# Pi_Interface.net
KiCad netlist of a schematic drawn in EAGLE
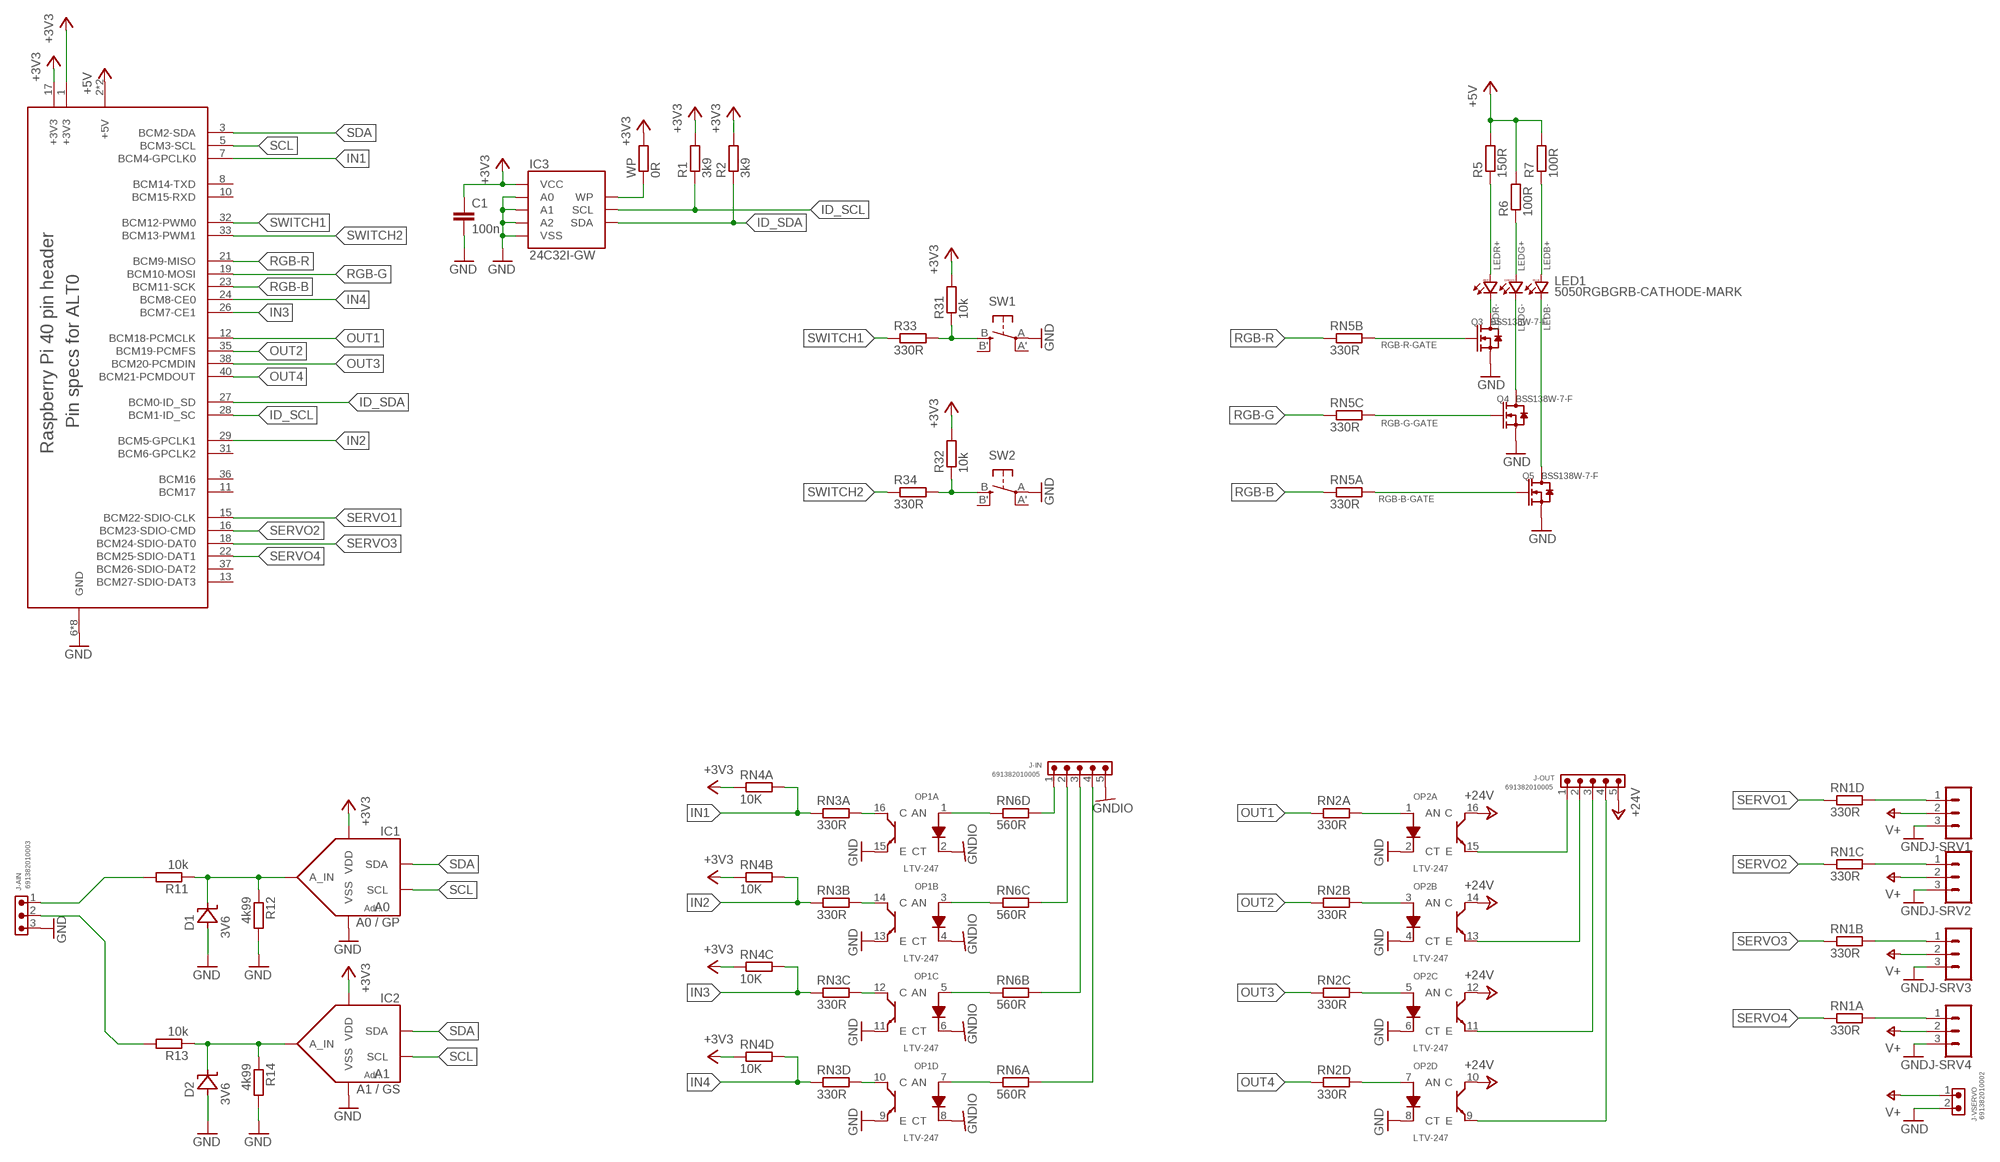
[diagram p0: schematic, sheet 1]

(export (version "E")
  (design (tool "Eeschema 10.0.6"))
  (components
    (comp (ref "C1")
      (value "100n")
      (footprint "eagle-import:C0603")
      (libsource (lib "eagle-import") (part "C-EUC0603"))
    )
    (comp (ref "D1")
      (value "3V6")
      (footprint "eagle-import:SOD3716X115N")
      (libsource (lib "eagle-import") (part "ZENERSOD-123"))
    )
    (comp (ref "D2")
      (value "3V6")
      (footprint "eagle-import:SOD3716X115N")
      (libsource (lib "eagle-import") (part "ZENERSOD-123"))
    )
    (comp (ref "IC1")
      (value "A0 / GP")
      (footprint "eagle-import:SOT95P280X145-5N")
      (fields (field (name "ADR") "A0"))
      (libsource (lib "eagle-import") (part "MCP3021T-E/OTA0"))
    )
    (comp (ref "IC2")
      (value "A1 / GS")
      (footprint "eagle-import:SOT95P280X145-5N")
      (fields (field (name "ADR") "A1"))
      (libsource (lib "eagle-import") (part "MCP3021T-E/OTA1"))
    )
    (comp (ref "IC3")
      (value "24C32I-GW")
      (footprint "eagle-import:SOIC127P600X175-8N")
      (libsource (lib "eagle-import") (part "24C32WI-G"))
    )
    (comp (ref "J-AIN")
      (value "691382010003")
      (footprint "eagle-import:691382010003")
      (libsource (lib "eagle-import") (part "691382010003"))
    )
    (comp (ref "J-IN")
      (value "691382010005")
      (footprint "eagle-import:691382010005")
      (libsource (lib "eagle-import") (part "691382010005"))
    )
    (comp (ref "J-OUT")
      (value "691382010005")
      (footprint "eagle-import:691382010005")
      (libsource (lib "eagle-import") (part "691382010005"))
    )
    (comp (ref "J-SRV1")
      (value "MA03-1")
      (footprint "eagle-import:MA03-1")
      (libsource (lib "eagle-import") (part "MA03-1"))
    )
    (comp (ref "J-SRV2")
      (value "MA03-1")
      (footprint "eagle-import:MA03-1")
      (libsource (lib "eagle-import") (part "MA03-1"))
    )
    (comp (ref "J-SRV3")
      (value "MA03-1")
      (footprint "eagle-import:MA03-1")
      (libsource (lib "eagle-import") (part "MA03-1"))
    )
    (comp (ref "J-SRV4")
      (value "MA03-1")
      (footprint "eagle-import:MA03-1")
      (libsource (lib "eagle-import") (part "MA03-1"))
    )
    (comp (ref "J-VSERVO")
      (value "691382010002")
      (footprint "eagle-import:691382010002")
      (libsource (lib "eagle-import") (part "691382010002"))
    )
    (comp (ref "J3")
      (value "RASPI-40HAT")
      (footprint "eagle-import:FE20-2")
      (libsource (lib "eagle-import") (part "RASPI-40HAT"))
    )
    (comp (ref "LED1")
      (value "5050RGBGRB-CATHODE-MARK")
      (footprint "eagle-import:CATH_MARK_5050_PLCC6")
      (libsource (lib "eagle-import") (part "5050RGBGRB-CATHODE-MARK"))
    )
    (comp (ref "OP1")
      (value "LTV-247")
      (footprint "eagle-import:SOIC127P675X220-16N")
      (fields (field (name "LCSC_PART") "C115451"))
      (libsource (lib "eagle-import") (part "LTV-247"))
    )
    (comp (ref "OP2")
      (value "LTV-247")
      (footprint "eagle-import:SOIC127P675X220-16N")
      (fields (field (name "LCSC_PART") "C115451"))
      (libsource (lib "eagle-import") (part "LTV-247"))
    )
    (comp (ref "Q3")
      (value "BSS138W-7-F")
      (footprint "eagle-import:SOT-23")
      (libsource (lib "eagle-import") (part "SMD-MOSFET-N-CH-50V-200MA-BSS138W-7-F(SOT-23)"))
    )
    (comp (ref "Q4")
      (value "BSS138W-7-F")
      (footprint "eagle-import:SOT-23")
      (libsource (lib "eagle-import") (part "SMD-MOSFET-N-CH-50V-200MA-BSS138W-7-F(SOT-23)"))
    )
    (comp (ref "Q5")
      (value "BSS138W-7-F")
      (footprint "eagle-import:SOT-23")
      (libsource (lib "eagle-import") (part "SMD-MOSFET-N-CH-50V-200MA-BSS138W-7-F(SOT-23)"))
    )
    (comp (ref "R1")
      (value "3k9")
      (footprint "eagle-import:R0603")
      (libsource (lib "eagle-import") (part "R-EU_R0603"))
    )
    (comp (ref "R2")
      (value "3k9")
      (footprint "eagle-import:R0603")
      (libsource (lib "eagle-import") (part "R-EU_R0603"))
    )
    (comp (ref "R5")
      (value "150R")
      (footprint "eagle-import:R0603")
      (libsource (lib "eagle-import") (part "R-EU_R0603"))
    )
    (comp (ref "R6")
      (value "100R")
      (footprint "eagle-import:R0603")
      (libsource (lib "eagle-import") (part "R-EU_R0603"))
    )
    (comp (ref "R7")
      (value "100R")
      (footprint "eagle-import:R0603")
      (libsource (lib "eagle-import") (part "R-EU_R0603"))
    )
    (comp (ref "R11")
      (value "10k")
      (footprint "eagle-import:R0603")
      (libsource (lib "eagle-import") (part "R-EU_R0603"))
    )
    (comp (ref "R12")
      (value "4k99")
      (footprint "eagle-import:R0603")
      (libsource (lib "eagle-import") (part "R-EU_R0603"))
    )
    (comp (ref "R13")
      (value "10k")
      (footprint "eagle-import:R0603")
      (libsource (lib "eagle-import") (part "R-EU_R0603"))
    )
    (comp (ref "R14")
      (value "4k99")
      (footprint "eagle-import:R0603")
      (libsource (lib "eagle-import") (part "R-EU_R0603"))
    )
    (comp (ref "R31")
      (value "10k")
      (footprint "eagle-import:R0603")
      (libsource (lib "eagle-import") (part "R-EU_R0603"))
    )
    (comp (ref "R32")
      (value "10k")
      (footprint "eagle-import:R0603")
      (libsource (lib "eagle-import") (part "R-EU_R0603"))
    )
    (comp (ref "R33")
      (value "330R")
      (footprint "eagle-import:R0603")
      (libsource (lib "eagle-import") (part "R-EU_R0603"))
    )
    (comp (ref "R34")
      (value "330R")
      (footprint "eagle-import:R0603")
      (libsource (lib "eagle-import") (part "R-EU_R0603"))
    )
    (comp (ref "RN1")
      (value "330R")
      (footprint "eagle-import:RESCAV80P315X160X60-8N")
      (fields (field (name "MANUFACTURER") "YAGEO") (field (name "MPN") "TC164-F*"))
      (libsource (lib "eagle-import") (part "R-NET4-1206C"))
    )
    (comp (ref "RN2")
      (value "330R")
      (footprint "eagle-import:RESCAV80P315X160X60-8N")
      (fields (field (name "MANUFACTURER") "YAGEO") (field (name "MPN") "TC164-F*"))
      (libsource (lib "eagle-import") (part "R-NET4-1206C"))
    )
    (comp (ref "RN3")
      (value "330R")
      (footprint "eagle-import:RESCAXS80P315X160X60-8N")
      (fields (field (name "MANUFACTURER") "YAGEO") (field (name "MPN") "YC164-F*"))
      (libsource (lib "eagle-import") (part "R-NET4-1206"))
    )
    (comp (ref "RN4")
      (value "10K")
      (footprint "eagle-import:RESCAXS80P315X160X60-8N")
      (fields (field (name "MANUFACTURER") "YAGEO") (field (name "MPN") "YC164-F*"))
      (libsource (lib "eagle-import") (part "R-NET4-1206"))
    )
    (comp (ref "RN5")
      (value "330R")
      (footprint "eagle-import:RESCAV80P315X160X60-8N")
      (fields (field (name "MANUFACTURER") "YAGEO") (field (name "MPN") "TC164-F*"))
      (libsource (lib "eagle-import") (part "R-NET4-1206C"))
    )
    (comp (ref "RN6")
      (value "560R")
      (footprint "eagle-import:RESCAXS80P315X160X60-8N")
      (fields (field (name "MANUFACTURER") "YAGEO") (field (name "MPN") "YC164-F*"))
      (libsource (lib "eagle-import") (part "R-NET4-1206"))
    )
    (comp (ref "SW1")
      (value "SPST_TACT-PT645")
      (footprint "eagle-import:PT645-SMT")
      (fields (field (name "MPN") "PTS645SM43SMTR92LFS"))
      (libsource (lib "eagle-import") (part "SPST_TACT-PT645"))
    )
    (comp (ref "SW2")
      (value "SPST_TACT-PT645")
      (footprint "eagle-import:PT645-SMT")
      (fields (field (name "MPN") "PTS645SM43SMTR92LFS"))
      (libsource (lib "eagle-import") (part "SPST_TACT-PT645"))
    )
    (comp (ref "WP")
      (value "0R")
      (footprint "eagle-import:R0603")
      (libsource (lib "eagle-import") (part "R-EU_R0603"))
    )
  )
  (nets
    (net (code "1") (name "+3V3") (class "Default")
      (node (ref "C1") (pin "1") (pinfunction "1_1") (pintype "passive"))
      (node (ref "IC1") (pin "1") (pinfunction "VDD_1") (pintype "bidirectional"))
      (node (ref "IC2") (pin "1") (pinfunction "VDD_1") (pintype "bidirectional"))
      (node (ref "IC3") (pin "8") (pinfunction "VCC_8") (pintype "bidirectional"))
      (node (ref "J3") (pin "1") (pinfunction "+3V3_1") (pintype "bidirectional"))
      (node (ref "J3") (pin "17") (pinfunction "+3V3_17") (pintype "bidirectional"))
      (node (ref "R1") (pin "2") (pinfunction "2_2") (pintype "passive"))
      (node (ref "R2") (pin "2") (pinfunction "2_2") (pintype "passive"))
      (node (ref "R31") (pin "2") (pinfunction "2_2") (pintype "passive"))
      (node (ref "R32") (pin "2") (pinfunction "2_2") (pintype "passive"))
      (node (ref "RN4") (pin "1") (pinfunction "1_1") (pintype "passive"))
      (node (ref "RN4") (pin "2") (pinfunction "1_2") (pintype "passive"))
      (node (ref "RN4") (pin "3") (pinfunction "1_3") (pintype "passive"))
      (node (ref "RN4") (pin "4") (pinfunction "1_4") (pintype "passive"))
      (node (ref "WP") (pin "2") (pinfunction "2_2") (pintype "passive"))
    )
    (net (code "2") (name "+5V") (class "Default")
      (node (ref "J3") (pin "2") (pinfunction "+5V_2") (pintype "bidirectional"))
      (node (ref "J3") (pin "4") (pinfunction "+5V_4") (pintype "bidirectional"))
      (node (ref "R5") (pin "2") (pinfunction "2_2") (pintype "passive"))
      (node (ref "R6") (pin "2") (pinfunction "2_2") (pintype "passive"))
      (node (ref "R7") (pin "2") (pinfunction "2_2") (pintype "passive"))
    )
    (net (code "3") (name "+24V") (class "Default")
      (node (ref "J-OUT") (pin "5") (pinfunction "5_5") (pintype "passive"))
      (node (ref "OP2") (pin "10") (pinfunction "C_10") (pintype "bidirectional"))
      (node (ref "OP2") (pin "12") (pinfunction "C_12") (pintype "bidirectional"))
      (node (ref "OP2") (pin "14") (pinfunction "C_14") (pintype "bidirectional"))
      (node (ref "OP2") (pin "16") (pinfunction "C_16") (pintype "bidirectional"))
    )
    (net (code "4") (name "/LEDB+") (class "Default")
      (node (ref "LED1") (pin "3") (pinfunction "B+_3") (pintype "passive"))
      (node (ref "R7") (pin "1") (pinfunction "1_1") (pintype "passive"))
    )
    (net (code "5") (name "/LEDB-") (class "Default")
      (node (ref "LED1") (pin "4") (pinfunction "B-_4") (pintype "passive"))
      (node (ref "Q5") (pin "3") (pinfunction "D_3") (pintype "passive"))
    )
    (net (code "6") (name "/LEDG+") (class "Default")
      (node (ref "LED1") (pin "1") (pinfunction "G+_1") (pintype "passive"))
      (node (ref "R6") (pin "1") (pinfunction "1_1") (pintype "passive"))
    )
    (net (code "7") (name "/LEDG-") (class "Default")
      (node (ref "LED1") (pin "6") (pinfunction "G-_6") (pintype "passive"))
      (node (ref "Q4") (pin "3") (pinfunction "D_3") (pintype "passive"))
    )
    (net (code "8") (name "/LEDR+") (class "Default")
      (node (ref "LED1") (pin "2") (pinfunction "R+_2") (pintype "passive"))
      (node (ref "R5") (pin "1") (pinfunction "1_1") (pintype "passive"))
    )
    (net (code "9") (name "/LEDR-") (class "Default")
      (node (ref "LED1") (pin "5") (pinfunction "R-_5") (pintype "passive"))
      (node (ref "Q3") (pin "3") (pinfunction "D_3") (pintype "passive"))
    )
    (net (code "10") (name "/RGB-B-GATE") (class "Default")
      (node (ref "Q5") (pin "1") (pinfunction "G_1") (pintype "passive"))
      (node (ref "RN5") (pin "8") (pinfunction "2_8") (pintype "passive"))
    )
    (net (code "11") (name "/RGB-G-GATE") (class "Default")
      (node (ref "Q4") (pin "1") (pinfunction "G_1") (pintype "passive"))
      (node (ref "RN5") (pin "6") (pinfunction "2_6") (pintype "passive"))
    )
    (net (code "12") (name "/RGB-R-GATE") (class "Default")
      (node (ref "Q3") (pin "1") (pinfunction "G_1") (pintype "passive"))
      (node (ref "RN5") (pin "7") (pinfunction "2_7") (pintype "passive"))
    )
    (net (code "13") (name "GND") (class "Default")
      (node (ref "C1") (pin "2") (pinfunction "2_2") (pintype "passive"))
      (node (ref "D1") (pin "2") (pinfunction "A_2") (pintype "passive"))
      (node (ref "D2") (pin "2") (pinfunction "A_2") (pintype "passive"))
      (node (ref "IC1") (pin "2") (pinfunction "VSS_2") (pintype "bidirectional"))
      (node (ref "IC2") (pin "2") (pinfunction "VSS_2") (pintype "bidirectional"))
      (node (ref "IC3") (pin "1") (pinfunction "A0_1") (pintype "bidirectional"))
      (node (ref "IC3") (pin "2") (pinfunction "A1_2") (pintype "bidirectional"))
      (node (ref "IC3") (pin "3") (pinfunction "A2_3") (pintype "bidirectional"))
      (node (ref "IC3") (pin "4") (pinfunction "VSS_4") (pintype "bidirectional"))
      (node (ref "J-AIN") (pin "3") (pinfunction "3_3") (pintype "passive"))
      (node (ref "J-SRV1") (pin "3") (pinfunction "3_3") (pintype "passive"))
      (node (ref "J-SRV2") (pin "3") (pinfunction "3_3") (pintype "passive"))
      (node (ref "J-SRV3") (pin "3") (pinfunction "3_3") (pintype "passive"))
      (node (ref "J-SRV4") (pin "3") (pinfunction "3_3") (pintype "passive"))
      (node (ref "J-VSERVO") (pin "2") (pinfunction "2_2") (pintype "passive"))
      (node (ref "J3") (pin "14") (pinfunction "GND_14") (pintype "bidirectional"))
      (node (ref "J3") (pin "20") (pinfunction "GND_20") (pintype "bidirectional"))
      (node (ref "J3") (pin "25") (pinfunction "GND_25") (pintype "bidirectional"))
      (node (ref "J3") (pin "30") (pinfunction "GND_30") (pintype "bidirectional"))
      (node (ref "J3") (pin "34") (pinfunction "GND_34") (pintype "bidirectional"))
      (node (ref "J3") (pin "39") (pinfunction "GND_39") (pintype "bidirectional"))
      (node (ref "J3") (pin "6") (pinfunction "GND_6") (pintype "bidirectional"))
      (node (ref "J3") (pin "9") (pinfunction "GND_9") (pintype "bidirectional"))
      (node (ref "OP1") (pin "11") (pinfunction "E_11") (pintype "bidirectional"))
      (node (ref "OP1") (pin "13") (pinfunction "E_13") (pintype "bidirectional"))
      (node (ref "OP1") (pin "15") (pinfunction "E_15") (pintype "bidirectional"))
      (node (ref "OP1") (pin "9") (pinfunction "E_9") (pintype "bidirectional"))
      (node (ref "OP2") (pin "2") (pinfunction "CT_2") (pintype "bidirectional"))
      (node (ref "OP2") (pin "4") (pinfunction "CT_4") (pintype "bidirectional"))
      (node (ref "OP2") (pin "6") (pinfunction "CT_6") (pintype "bidirectional"))
      (node (ref "OP2") (pin "8") (pinfunction "CT_8") (pintype "bidirectional"))
      (node (ref "Q3") (pin "2") (pinfunction "S_2") (pintype "passive"))
      (node (ref "Q4") (pin "2") (pinfunction "S_2") (pintype "passive"))
      (node (ref "Q5") (pin "2") (pinfunction "S_2") (pintype "passive"))
      (node (ref "R12") (pin "2") (pinfunction "2_2") (pintype "passive"))
      (node (ref "R14") (pin "2") (pinfunction "2_2") (pintype "passive"))
      (node (ref "SW1") (pin "A") (pinfunction "P_A") (pintype "passive"))
      (node (ref "SW2") (pin "A") (pinfunction "P_A") (pintype "passive"))
    )
    (net (code "14") (name "GNDIO") (class "Default")
      (node (ref "J-IN") (pin "5") (pinfunction "5_5") (pintype "passive"))
      (node (ref "OP1") (pin "2") (pinfunction "CT_2") (pintype "bidirectional"))
      (node (ref "OP1") (pin "4") (pinfunction "CT_4") (pintype "bidirectional"))
      (node (ref "OP1") (pin "6") (pinfunction "CT_6") (pintype "bidirectional"))
      (node (ref "OP1") (pin "8") (pinfunction "CT_8") (pintype "bidirectional"))
    )
    (net (code "15") (name "ID_SCL") (class "Default")
      (node (ref "IC3") (pin "6") (pinfunction "SCL_6") (pintype "bidirectional"))
      (node (ref "J3") (pin "28") (pinfunction "BCM1-ID_SC_28") (pintype "bidirectional"))
      (node (ref "R1") (pin "1") (pinfunction "1_1") (pintype "passive"))
    )
    (net (code "16") (name "ID_SDA") (class "Default")
      (node (ref "IC3") (pin "5") (pinfunction "SDA_5") (pintype "bidirectional"))
      (node (ref "J3") (pin "27") (pinfunction "BCM0-ID_SD_27") (pintype "bidirectional"))
      (node (ref "R2") (pin "1") (pinfunction "1_1") (pintype "passive"))
    )
    (net (code "17") (name "IN1") (class "Default")
      (node (ref "J3") (pin "7") (pinfunction "BCM4-GPCLK0_7") (pintype "bidirectional"))
      (node (ref "RN3") (pin "1") (pinfunction "1_1") (pintype "passive"))
      (node (ref "RN4") (pin "8") (pinfunction "2_8") (pintype "passive"))
    )
    (net (code "18") (name "IN2") (class "Default")
      (node (ref "J3") (pin "29") (pinfunction "BCM5-GPCLK1_29") (pintype "bidirectional"))
      (node (ref "RN3") (pin "2") (pinfunction "1_2") (pintype "passive"))
      (node (ref "RN4") (pin "7") (pinfunction "2_7") (pintype "passive"))
    )
    (net (code "19") (name "IN3") (class "Default")
      (node (ref "J3") (pin "26") (pinfunction "BCM7-CE1_26") (pintype "bidirectional"))
      (node (ref "RN3") (pin "3") (pinfunction "1_3") (pintype "passive"))
      (node (ref "RN4") (pin "6") (pinfunction "2_6") (pintype "passive"))
    )
    (net (code "20") (name "IN4") (class "Default")
      (node (ref "J3") (pin "24") (pinfunction "BCM8-CE0_24") (pintype "bidirectional"))
      (node (ref "RN3") (pin "4") (pinfunction "1_4") (pintype "passive"))
      (node (ref "RN4") (pin "5") (pinfunction "2_5") (pintype "passive"))
    )
    (net (code "21") (name "Net-(D1-C)") (class "Default")
      (node (ref "D1") (pin "1") (pinfunction "C_1") (pintype "passive"))
      (node (ref "IC1") (pin "3") (pinfunction "A_IN_3") (pintype "bidirectional"))
      (node (ref "R11") (pin "1") (pinfunction "1_1") (pintype "passive"))
      (node (ref "R12") (pin "1") (pinfunction "1_1") (pintype "passive"))
    )
    (net (code "22") (name "Net-(D2-C)") (class "Default")
      (node (ref "D2") (pin "1") (pinfunction "C_1") (pintype "passive"))
      (node (ref "IC2") (pin "3") (pinfunction "A_IN_3") (pintype "bidirectional"))
      (node (ref "R13") (pin "1") (pinfunction "1_1") (pintype "passive"))
      (node (ref "R14") (pin "1") (pinfunction "1_1") (pintype "passive"))
    )
    (net (code "23") (name "Net-(IC3-WP)") (class "Default")
      (node (ref "IC3") (pin "7") (pinfunction "WP_7") (pintype "bidirectional"))
      (node (ref "WP") (pin "1") (pinfunction "1_1") (pintype "passive"))
    )
    (net (code "24") (name "Net-(J-AIN-Pad1)") (class "Default")
      (node (ref "J-AIN") (pin "1") (pinfunction "1_1") (pintype "passive"))
      (node (ref "R11") (pin "2") (pinfunction "2_2") (pintype "passive"))
    )
    (net (code "25") (name "Net-(J-AIN-Pad2)") (class "Default")
      (node (ref "J-AIN") (pin "2") (pinfunction "2_2") (pintype "passive"))
      (node (ref "R13") (pin "2") (pinfunction "2_2") (pintype "passive"))
    )
    (net (code "26") (name "Net-(OP1A-AN)") (class "Default")
      (node (ref "OP1") (pin "1") (pinfunction "AN_1") (pintype "bidirectional"))
      (node (ref "RN6") (pin "4") (pinfunction "1_4") (pintype "passive"))
    )
    (net (code "27") (name "Net-(OP1A-C)") (class "Default")
      (node (ref "OP1") (pin "16") (pinfunction "C_16") (pintype "bidirectional"))
      (node (ref "RN3") (pin "8") (pinfunction "2_8") (pintype "passive"))
    )
    (net (code "28") (name "Net-(OP1B-AN)") (class "Default")
      (node (ref "OP1") (pin "3") (pinfunction "AN_3") (pintype "bidirectional"))
      (node (ref "RN6") (pin "3") (pinfunction "1_3") (pintype "passive"))
    )
    (net (code "29") (name "Net-(OP1B-C)") (class "Default")
      (node (ref "OP1") (pin "14") (pinfunction "C_14") (pintype "bidirectional"))
      (node (ref "RN3") (pin "7") (pinfunction "2_7") (pintype "passive"))
    )
    (net (code "30") (name "Net-(OP1C-AN)") (class "Default")
      (node (ref "OP1") (pin "5") (pinfunction "AN_5") (pintype "bidirectional"))
      (node (ref "RN6") (pin "2") (pinfunction "1_2") (pintype "passive"))
    )
    (net (code "31") (name "Net-(OP1C-C)") (class "Default")
      (node (ref "OP1") (pin "12") (pinfunction "C_12") (pintype "bidirectional"))
      (node (ref "RN3") (pin "6") (pinfunction "2_6") (pintype "passive"))
    )
    (net (code "32") (name "Net-(OP1D-AN)") (class "Default")
      (node (ref "OP1") (pin "7") (pinfunction "AN_7") (pintype "bidirectional"))
      (node (ref "RN6") (pin "1") (pinfunction "1_1") (pintype "passive"))
    )
    (net (code "33") (name "Net-(OP1D-C)") (class "Default")
      (node (ref "OP1") (pin "10") (pinfunction "C_10") (pintype "bidirectional"))
      (node (ref "RN3") (pin "5") (pinfunction "2_5") (pintype "passive"))
    )
    (net (code "34") (name "Net-(OP2A-AN)") (class "Default")
      (node (ref "OP2") (pin "1") (pinfunction "AN_1") (pintype "bidirectional"))
      (node (ref "RN2") (pin "8") (pinfunction "2_8") (pintype "passive"))
    )
    (net (code "35") (name "Net-(OP2A-E)") (class "Default")
      (node (ref "J-OUT") (pin "1") (pinfunction "1_1") (pintype "passive"))
      (node (ref "OP2") (pin "15") (pinfunction "E_15") (pintype "bidirectional"))
    )
    (net (code "36") (name "Net-(OP2B-AN)") (class "Default")
      (node (ref "OP2") (pin "3") (pinfunction "AN_3") (pintype "bidirectional"))
      (node (ref "RN2") (pin "7") (pinfunction "2_7") (pintype "passive"))
    )
    (net (code "37") (name "Net-(OP2B-E)") (class "Default")
      (node (ref "J-OUT") (pin "2") (pinfunction "2_2") (pintype "passive"))
      (node (ref "OP2") (pin "13") (pinfunction "E_13") (pintype "bidirectional"))
    )
    (net (code "38") (name "Net-(OP2C-AN)") (class "Default")
      (node (ref "OP2") (pin "5") (pinfunction "AN_5") (pintype "bidirectional"))
      (node (ref "RN2") (pin "6") (pinfunction "2_6") (pintype "passive"))
    )
    (net (code "39") (name "Net-(OP2C-E)") (class "Default")
      (node (ref "J-OUT") (pin "3") (pinfunction "3_3") (pintype "passive"))
      (node (ref "OP2") (pin "11") (pinfunction "E_11") (pintype "bidirectional"))
    )
    (net (code "40") (name "Net-(OP2D-AN)") (class "Default")
      (node (ref "OP2") (pin "7") (pinfunction "AN_7") (pintype "bidirectional"))
      (node (ref "RN2") (pin "5") (pinfunction "2_5") (pintype "passive"))
    )
    (net (code "41") (name "Net-(OP2D-E)") (class "Default")
      (node (ref "J-OUT") (pin "4") (pinfunction "4_4") (pintype "passive"))
      (node (ref "OP2") (pin "9") (pinfunction "E_9") (pintype "bidirectional"))
    )
    (net (code "42") (name "Net-(RN1A-2)") (class "Default")
      (node (ref "J-SRV4") (pin "1") (pinfunction "1_1") (pintype "passive"))
      (node (ref "RN1") (pin "8") (pinfunction "2_8") (pintype "passive"))
    )
    (net (code "43") (name "Net-(RN1B-2)") (class "Default")
      (node (ref "J-SRV3") (pin "1") (pinfunction "1_1") (pintype "passive"))
      (node (ref "RN1") (pin "7") (pinfunction "2_7") (pintype "passive"))
    )
    (net (code "44") (name "Net-(RN1C-2)") (class "Default")
      (node (ref "J-SRV2") (pin "1") (pinfunction "1_1") (pintype "passive"))
      (node (ref "RN1") (pin "6") (pinfunction "2_6") (pintype "passive"))
    )
    (net (code "45") (name "Net-(RN1D-2)") (class "Default")
      (node (ref "J-SRV1") (pin "1") (pinfunction "1_1") (pintype "passive"))
      (node (ref "RN1") (pin "5") (pinfunction "2_5") (pintype "passive"))
    )
    (net (code "46") (name "Net-(RN6A-2)") (class "Default")
      (node (ref "J-IN") (pin "4") (pinfunction "4_4") (pintype "passive"))
      (node (ref "RN6") (pin "8") (pinfunction "2_8") (pintype "passive"))
    )
    (net (code "47") (name "Net-(RN6B-2)") (class "Default")
      (node (ref "J-IN") (pin "3") (pinfunction "3_3") (pintype "passive"))
      (node (ref "RN6") (pin "7") (pinfunction "2_7") (pintype "passive"))
    )
    (net (code "48") (name "Net-(RN6C-2)") (class "Default")
      (node (ref "J-IN") (pin "2") (pinfunction "2_2") (pintype "passive"))
      (node (ref "RN6") (pin "6") (pinfunction "2_6") (pintype "passive"))
    )
    (net (code "49") (name "Net-(RN6D-2)") (class "Default")
      (node (ref "J-IN") (pin "1") (pinfunction "1_1") (pintype "passive"))
      (node (ref "RN6") (pin "5") (pinfunction "2_5") (pintype "passive"))
    )
    (net (code "50") (name "Net-(SW1-S)") (class "Default")
      (node (ref "R31") (pin "1") (pinfunction "1_1") (pintype "passive"))
      (node (ref "R33") (pin "2") (pinfunction "2_2") (pintype "passive"))
      (node (ref "SW1") (pin "B") (pinfunction "S_B") (pintype "passive"))
    )
    (net (code "51") (name "Net-(SW2-S)") (class "Default")
      (node (ref "R32") (pin "1") (pinfunction "1_1") (pintype "passive"))
      (node (ref "R34") (pin "2") (pinfunction "2_2") (pintype "passive"))
      (node (ref "SW2") (pin "B") (pinfunction "S_B") (pintype "passive"))
    )
    (net (code "52") (name "OUT1") (class "Default")
      (node (ref "J3") (pin "12") (pinfunction "BCM18-PCMCLK_12") (pintype "bidirectional"))
      (node (ref "RN2") (pin "1") (pinfunction "1_1") (pintype "passive"))
    )
    (net (code "53") (name "OUT2") (class "Default")
      (node (ref "J3") (pin "35") (pinfunction "BCM19-PCMFS_35") (pintype "bidirectional"))
      (node (ref "RN2") (pin "2") (pinfunction "1_2") (pintype "passive"))
    )
    (net (code "54") (name "OUT3") (class "Default")
      (node (ref "J3") (pin "38") (pinfunction "BCM20-PCMDIN_38") (pintype "bidirectional"))
      (node (ref "RN2") (pin "3") (pinfunction "1_3") (pintype "passive"))
    )
    (net (code "55") (name "OUT4") (class "Default")
      (node (ref "J3") (pin "40") (pinfunction "BCM21-PCMDOUT_40") (pintype "bidirectional"))
      (node (ref "RN2") (pin "4") (pinfunction "1_4") (pintype "passive"))
    )
    (net (code "56") (name "RGB-B") (class "Default")
      (node (ref "J3") (pin "23") (pinfunction "BCM11-SCK_23") (pintype "bidirectional"))
      (node (ref "RN5") (pin "1") (pinfunction "1_1") (pintype "passive"))
    )
    (net (code "57") (name "RGB-G") (class "Default")
      (node (ref "J3") (pin "19") (pinfunction "BCM10-MOSI_19") (pintype "bidirectional"))
      (node (ref "RN5") (pin "3") (pinfunction "1_3") (pintype "passive"))
    )
    (net (code "58") (name "RGB-R") (class "Default")
      (node (ref "J3") (pin "21") (pinfunction "BCM9-MISO_21") (pintype "bidirectional"))
      (node (ref "RN5") (pin "2") (pinfunction "1_2") (pintype "passive"))
    )
    (net (code "59") (name "SCL") (class "Default")
      (node (ref "IC1") (pin "5") (pinfunction "SCL_5") (pintype "bidirectional"))
      (node (ref "IC2") (pin "5") (pinfunction "SCL_5") (pintype "bidirectional"))
      (node (ref "J3") (pin "5") (pinfunction "BCM3-SCL_5") (pintype "bidirectional"))
    )
    (net (code "60") (name "SDA") (class "Default")
      (node (ref "IC1") (pin "4") (pinfunction "SDA_4") (pintype "bidirectional"))
      (node (ref "IC2") (pin "4") (pinfunction "SDA_4") (pintype "bidirectional"))
      (node (ref "J3") (pin "3") (pinfunction "BCM2-SDA_3") (pintype "bidirectional"))
    )
    (net (code "61") (name "SERVO1") (class "Default")
      (node (ref "J3") (pin "15") (pinfunction "BCM22-SDIO-CLK_15") (pintype "bidirectional"))
      (node (ref "RN1") (pin "4") (pinfunction "1_4") (pintype "passive"))
    )
    (net (code "62") (name "SERVO2") (class "Default")
      (node (ref "J3") (pin "16") (pinfunction "BCM23-SDIO-CMD_16") (pintype "bidirectional"))
      (node (ref "RN1") (pin "3") (pinfunction "1_3") (pintype "passive"))
    )
    (net (code "63") (name "SERVO3") (class "Default")
      (node (ref "J3") (pin "18") (pinfunction "BCM24-SDIO-DAT0_18") (pintype "bidirectional"))
      (node (ref "RN1") (pin "2") (pinfunction "1_2") (pintype "passive"))
    )
    (net (code "64") (name "SERVO4") (class "Default")
      (node (ref "J3") (pin "22") (pinfunction "BCM25-SDIO-DAT1_22") (pintype "bidirectional"))
      (node (ref "RN1") (pin "1") (pinfunction "1_1") (pintype "passive"))
    )
    (net (code "65") (name "SWITCH1") (class "Default")
      (node (ref "J3") (pin "32") (pinfunction "BCM12-PWM0_32") (pintype "bidirectional"))
      (node (ref "R33") (pin "1") (pinfunction "1_1") (pintype "passive"))
    )
    (net (code "66") (name "SWITCH2") (class "Default")
      (node (ref "J3") (pin "33") (pinfunction "BCM13-PWM1_33") (pintype "bidirectional"))
      (node (ref "R34") (pin "1") (pinfunction "1_1") (pintype "passive"))
    )
    (net (code "67") (name "V+") (class "Default")
      (node (ref "J-SRV1") (pin "2") (pinfunction "2_2") (pintype "passive"))
      (node (ref "J-SRV2") (pin "2") (pinfunction "2_2") (pintype "passive"))
      (node (ref "J-SRV3") (pin "2") (pinfunction "2_2") (pintype "passive"))
      (node (ref "J-SRV4") (pin "2") (pinfunction "2_2") (pintype "passive"))
      (node (ref "J-VSERVO") (pin "1") (pinfunction "1_1") (pintype "passive"))
    )
    (net (code "68") (name "unconnected-(J3-BCM6-GPCLK2-Pad31)") (class "Default")
      (node (ref "J3") (pin "31") (pinfunction "BCM6-GPCLK2_31") (pintype "bidirectional"))
    )
    (net (code "69") (name "unconnected-(J3-BCM14-TXD-Pad8)") (class "Default")
      (node (ref "J3") (pin "8") (pinfunction "BCM14-TXD_8") (pintype "bidirectional"))
    )
    (net (code "70") (name "unconnected-(J3-BCM15-RXD-Pad10)") (class "Default")
      (node (ref "J3") (pin "10") (pinfunction "BCM15-RXD_10") (pintype "bidirectional"))
    )
    (net (code "71") (name "unconnected-(J3-BCM16-Pad36)") (class "Default")
      (node (ref "J3") (pin "36") (pinfunction "BCM16_36") (pintype "bidirectional"))
    )
    (net (code "72") (name "unconnected-(J3-BCM17-Pad11)") (class "Default")
      (node (ref "J3") (pin "11") (pinfunction "BCM17_11") (pintype "bidirectional"))
    )
    (net (code "73") (name "unconnected-(J3-BCM26-SDIO-DAT2-Pad37)") (class "Default")
      (node (ref "J3") (pin "37") (pinfunction "BCM26-SDIO-DAT2_37") (pintype "bidirectional"))
    )
    (net (code "74") (name "unconnected-(J3-BCM27-SDIO-DAT3-Pad13)") (class "Default")
      (node (ref "J3") (pin "13") (pinfunction "BCM27-SDIO-DAT3_13") (pintype "bidirectional"))
    )
    (net (code "75") (name "unconnected-(SW1-P1-PadA')") (class "Default")
      (node (ref "SW1") (pin "A'") (pinfunction "P1_A'") (pintype "passive"))
    )
    (net (code "76") (name "unconnected-(SW1-S1-PadB')") (class "Default")
      (node (ref "SW1") (pin "B'") (pinfunction "S1_B'") (pintype "passive"))
    )
    (net (code "77") (name "unconnected-(SW2-P1-PadA')") (class "Default")
      (node (ref "SW2") (pin "A'") (pinfunction "P1_A'") (pintype "passive"))
    )
    (net (code "78") (name "unconnected-(SW2-S1-PadB')") (class "Default")
      (node (ref "SW2") (pin "B'") (pinfunction "S1_B'") (pintype "passive"))
    )
  )
)
